# LiPo_Booster_v2_0.net
KiCad netlist of a schematic drawn in EAGLE
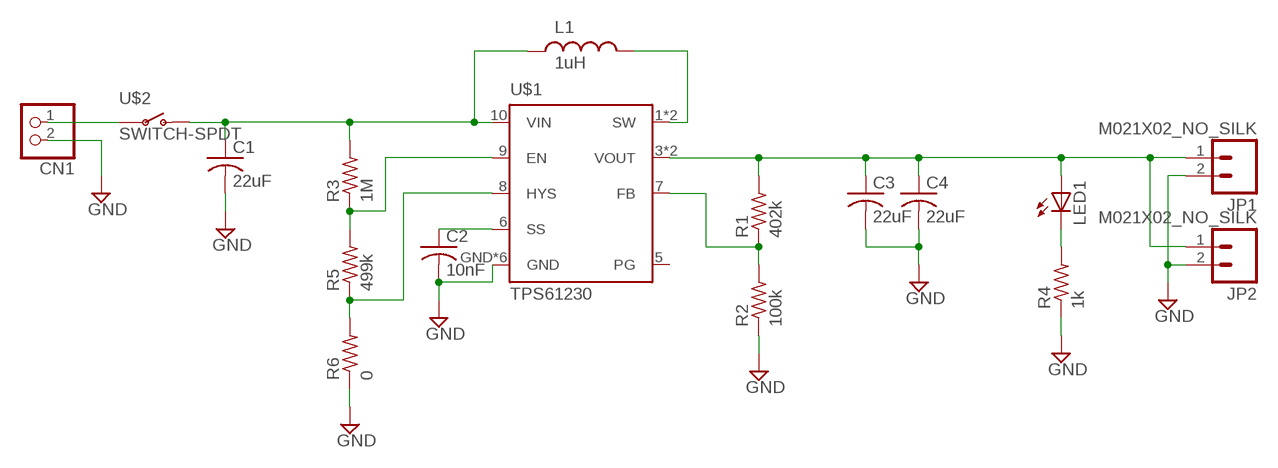
[diagram p0: schematic, sheet 1]

(export (version "E")
  (design (tool "Eeschema 10.0.6"))
  (components
    (comp (ref "C1")
      (value "22uF")
      (footprint "eagle-import:C0603K")
      (libsource (lib "eagle-import") (part "C-USC0603K"))
    )
    (comp (ref "C2")
      (value "10nF")
      (footprint "eagle-import:C0603K")
      (libsource (lib "eagle-import") (part "C-USC0603K"))
    )
    (comp (ref "C3")
      (value "22uF")
      (footprint "eagle-import:C0603K")
      (libsource (lib "eagle-import") (part "C-USC0603K"))
    )
    (comp (ref "C4")
      (value "22uF")
      (footprint "eagle-import:C0603K")
      (libsource (lib "eagle-import") (part "C-USC0603K"))
    )
    (comp (ref "CN1")
      (value "JST_2PIN-SMT-RA")
      (footprint "eagle-import:JST-PH-2-SMT-RA")
      (libsource (lib "eagle-import") (part "JST_2PIN-SMT-RA"))
    )
    (comp (ref "JP1")
      (value "M021X02_NO_SILK")
      (footprint "eagle-import:1X02_NO_SILK")
      (libsource (lib "eagle-import") (part "M021X02_NO_SILK"))
    )
    (comp (ref "JP2")
      (value "M021X02_NO_SILK")
      (footprint "eagle-import:1X02_NO_SILK")
      (libsource (lib "eagle-import") (part "M021X02_NO_SILK"))
    )
    (comp (ref "L1")
      (value "1uH")
      (footprint "eagle-import:XFL4020")
      (libsource (lib "eagle-import") (part "XFL4020"))
    )
    (comp (ref "LED1")
      (value "LEDCHIPLED_0603")
      (footprint "eagle-import:CHIPLED_0603")
      (libsource (lib "eagle-import") (part "LEDCHIPLED_0603"))
    )
    (comp (ref "R1")
      (value "402k")
      (footprint "eagle-import:R0603")
      (libsource (lib "eagle-import") (part "R-US_R0603"))
    )
    (comp (ref "R2")
      (value "100k")
      (footprint "eagle-import:R0603")
      (libsource (lib "eagle-import") (part "R-US_R0603"))
    )
    (comp (ref "R3")
      (value "1M")
      (footprint "eagle-import:R0603")
      (libsource (lib "eagle-import") (part "R-US_R0603"))
    )
    (comp (ref "R4")
      (value "1k")
      (footprint "eagle-import:R0603")
      (libsource (lib "eagle-import") (part "R-US_R0603"))
    )
    (comp (ref "R5")
      (value "499k")
      (footprint "eagle-import:R0603")
      (libsource (lib "eagle-import") (part "R-US_R0603"))
    )
    (comp (ref "R6")
      (value "0")
      (footprint "eagle-import:R0603")
      (libsource (lib "eagle-import") (part "R-US_R0603"))
    )
    (comp (ref "U$1")
      (value "TPS61230")
      (footprint "eagle-import:DRC-S-PVSON-N11")
      (libsource (lib "eagle-import") (part "TPS61230"))
    )
    (comp (ref "U$2")
      (value "SWITCH-SPDT")
      (footprint "eagle-import:JS102011")
      (libsource (lib "eagle-import") (part "SWITCH-SPDT"))
    )
  )
  (nets
    (net (code "1") (name "/PG") (class "Default")
      (node (ref "U$1") (pin "5") (pinfunction "PG_5") (pintype "power_in"))
    )
    (net (code "2") (name "GND") (class "Default")
      (node (ref "C1") (pin "2") (pinfunction "2_2") (pintype "passive"))
      (node (ref "C2") (pin "2") (pinfunction "2_2") (pintype "passive"))
      (node (ref "C3") (pin "2") (pinfunction "2_2") (pintype "passive"))
      (node (ref "C4") (pin "2") (pinfunction "2_2") (pintype "passive"))
      (node (ref "CN1") (pin "2") (pinfunction "1_2") (pintype "passive"))
      (node (ref "JP1") (pin "2") (pinfunction "2_2") (pintype "passive"))
      (node (ref "JP2") (pin "2") (pinfunction "2_2") (pintype "passive"))
      (node (ref "R2") (pin "1") (pinfunction "1_1") (pintype "passive"))
      (node (ref "R4") (pin "1") (pinfunction "1_1") (pintype "passive"))
      (node (ref "R6") (pin "1") (pinfunction "1_1") (pintype "passive"))
      (node (ref "U$1") (pin "GND") (pinfunction "GND_GND") (pintype "power_in"))
      (node (ref "U$1") (pin "GND@1") (pinfunction "GND_GND@1") (pintype "power_in"))
      (node (ref "U$1") (pin "GND@2") (pinfunction "GND_GND@2") (pintype "power_in"))
      (node (ref "U$1") (pin "GND@3") (pinfunction "GND_GND@3") (pintype "power_in"))
      (node (ref "U$1") (pin "GND@4") (pinfunction "GND_GND@4") (pintype "power_in"))
      (node (ref "U$1") (pin "GND@5") (pinfunction "GND_GND@5") (pintype "power_in"))
    )
    (net (code "3") (name "Net-(C3-Pad1)") (class "Default")
      (node (ref "C3") (pin "1") (pinfunction "1_1") (pintype "passive"))
      (node (ref "C4") (pin "1") (pinfunction "1_1") (pintype "passive"))
      (node (ref "JP1") (pin "1") (pinfunction "1_1") (pintype "passive"))
      (node (ref "JP2") (pin "1") (pinfunction "1_1") (pintype "passive"))
      (node (ref "LED1") (pin "A") (pinfunction "A_A") (pintype "passive"))
      (node (ref "R1") (pin "2") (pinfunction "2_2") (pintype "passive"))
      (node (ref "U$1") (pin "3") (pinfunction "VOUT_3") (pintype "passive"))
      (node (ref "U$1") (pin "4") (pinfunction "VOUT_4") (pintype "passive"))
    )
    (net (code "4") (name "Net-(CN1-2)") (class "Default")
      (node (ref "CN1") (pin "1") (pinfunction "2_1") (pintype "passive"))
      (node (ref "U$2") (pin "P$3") (pinfunction "P_P$3") (pintype "passive"))
    )
    (net (code "5") (name "Net-(L1-1)") (class "Default")
      (node (ref "C1") (pin "1") (pinfunction "1_1") (pintype "passive"))
      (node (ref "L1") (pin "P$1") (pinfunction "1_P$1") (pintype "passive"))
      (node (ref "R3") (pin "2") (pinfunction "2_2") (pintype "passive"))
      (node (ref "U$1") (pin "10") (pinfunction "VIN_10") (pintype "input"))
      (node (ref "U$2") (pin "P$2") (pinfunction "O_P$2") (pintype "passive"))
    )
    (net (code "6") (name "Net-(L1-2)") (class "Default")
      (node (ref "L1") (pin "P$2") (pinfunction "2_P$2") (pintype "passive"))
      (node (ref "U$1") (pin "1") (pinfunction "SW_1") (pintype "input"))
      (node (ref "U$1") (pin "2") (pinfunction "SW_2") (pintype "input"))
    )
    (net (code "7") (name "Net-(LED1-PadC)") (class "Default")
      (node (ref "LED1") (pin "C") (pinfunction "C_C") (pintype "passive"))
      (node (ref "R4") (pin "2") (pinfunction "2_2") (pintype "passive"))
    )
    (net (code "8") (name "Net-(U$1-EN)") (class "Default")
      (node (ref "R3") (pin "1") (pinfunction "1_1") (pintype "passive"))
      (node (ref "R5") (pin "2") (pinfunction "2_2") (pintype "passive"))
      (node (ref "U$1") (pin "9") (pinfunction "EN_9") (pintype "input"))
    )
    (net (code "9") (name "Net-(U$1-FB)") (class "Default")
      (node (ref "R1") (pin "1") (pinfunction "1_1") (pintype "passive"))
      (node (ref "R2") (pin "2") (pinfunction "2_2") (pintype "passive"))
      (node (ref "U$1") (pin "7") (pinfunction "FB_7") (pintype "input"))
    )
    (net (code "10") (name "Net-(U$1-HYS)") (class "Default")
      (node (ref "R5") (pin "1") (pinfunction "1_1") (pintype "passive"))
      (node (ref "R6") (pin "2") (pinfunction "2_2") (pintype "passive"))
      (node (ref "U$1") (pin "8") (pinfunction "HYS_8") (pintype "input"))
    )
    (net (code "11") (name "Net-(U$1-SS)") (class "Default")
      (node (ref "C2") (pin "1") (pinfunction "1_1") (pintype "passive"))
      (node (ref "U$1") (pin "6") (pinfunction "SS_6") (pintype "input"))
    )
  )
)
